# TactSwitch_SCH.net
KiCad netlist of a schematic drawn in Altium Designer
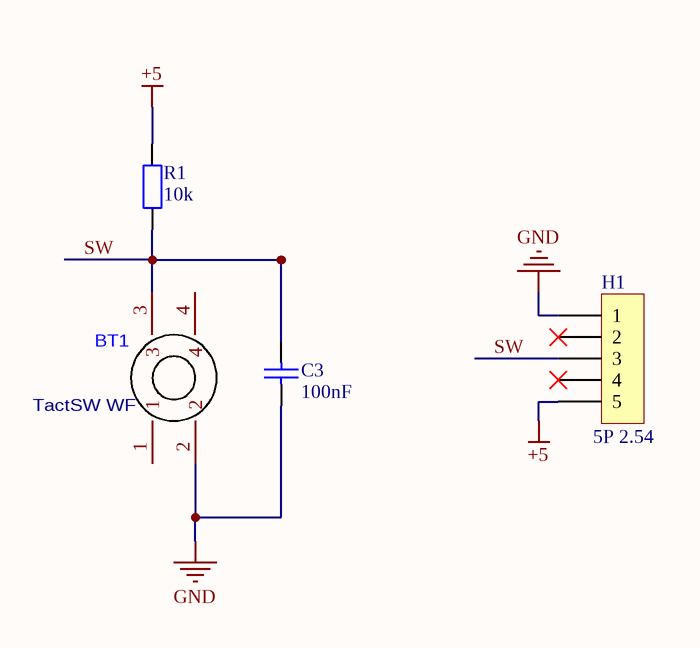
[diagram p0: TactSwitch_SCH.SchDoc]

(export (version "E")
  (design (tool "Eeschema 10.0.6"))
  (components
    (comp (ref "BT1")
      (value "TactSW WF")
      (footprint "12X12 BUTTOM red")
      (description "WaterProof TactSW")
      (libsource (lib "namnt_Lib") (part "Nut Nhan 4 chan 12x12"))
    )
    (comp (ref "C3")
      (value "100nF")
      (footprint "tu 0603")
      (description "Dán")
      (libsource (lib "namnt_Lib") (part "Tu 0603 104 50V 10%"))
    )
    (comp (ref "H1")
      (value "5P 2.54")
      (footprint "Header 5P DC 2.54")
      (description "Cắm")
      (libsource (lib "namnt_Lib") (part "Header 5P 2.54 Duc Cong"))
    )
    (comp (ref "R1")
      (value "10k")
      (footprint "tro smd 0603")
      (description "Dán")
      (libsource (lib "namnt_Lib") (part "Tro 0603 1% 10k"))
    )
  )
  (nets
    (net (code "1") (name "+5") (class "Default")
      (node (ref "H1") (pin "5") (pinfunction "5_5") (pintype "passive"))
      (node (ref "R1") (pin "2") (pinfunction "2_2") (pintype "passive"))
    )
    (net (code "2") (name "/SW") (class "Default")
      (node (ref "BT1") (pin "3") (pinfunction "3_3") (pintype "passive"))
      (node (ref "C3") (pin "1") (pinfunction "1_1") (pintype "passive"))
      (node (ref "H1") (pin "3") (pinfunction "3_3") (pintype "passive"))
      (node (ref "R1") (pin "1") (pinfunction "1_1") (pintype "passive"))
    )
    (net (code "3") (name "GND") (class "Default")
      (node (ref "BT1") (pin "2") (pinfunction "2_2") (pintype "passive"))
      (node (ref "C3") (pin "2") (pinfunction "2_2") (pintype "passive"))
      (node (ref "H1") (pin "1") (pinfunction "1_1") (pintype "passive"))
    )
    (net (code "4") (name "unconnected-(BT1-Pad1)") (class "Default")
      (node (ref "BT1") (pin "1") (pinfunction "1_1") (pintype "passive"))
    )
    (net (code "5") (name "unconnected-(BT1-Pad4)") (class "Default")
      (node (ref "BT1") (pin "4") (pinfunction "4_4") (pintype "passive"))
    )
    (net (code "6") (name "unconnected-(H1-Pad2)") (class "Default")
      (node (ref "H1") (pin "2") (pinfunction "2_2") (pintype "passive+no_connect"))
    )
    (net (code "7") (name "unconnected-(H1-Pad4)") (class "Default")
      (node (ref "H1") (pin "4") (pinfunction "4_4") (pintype "passive+no_connect"))
    )
  )
)
